# MCB-Wise-1530-v2_0_1.net
KiCad netlist of a schematic drawn in EAGLE
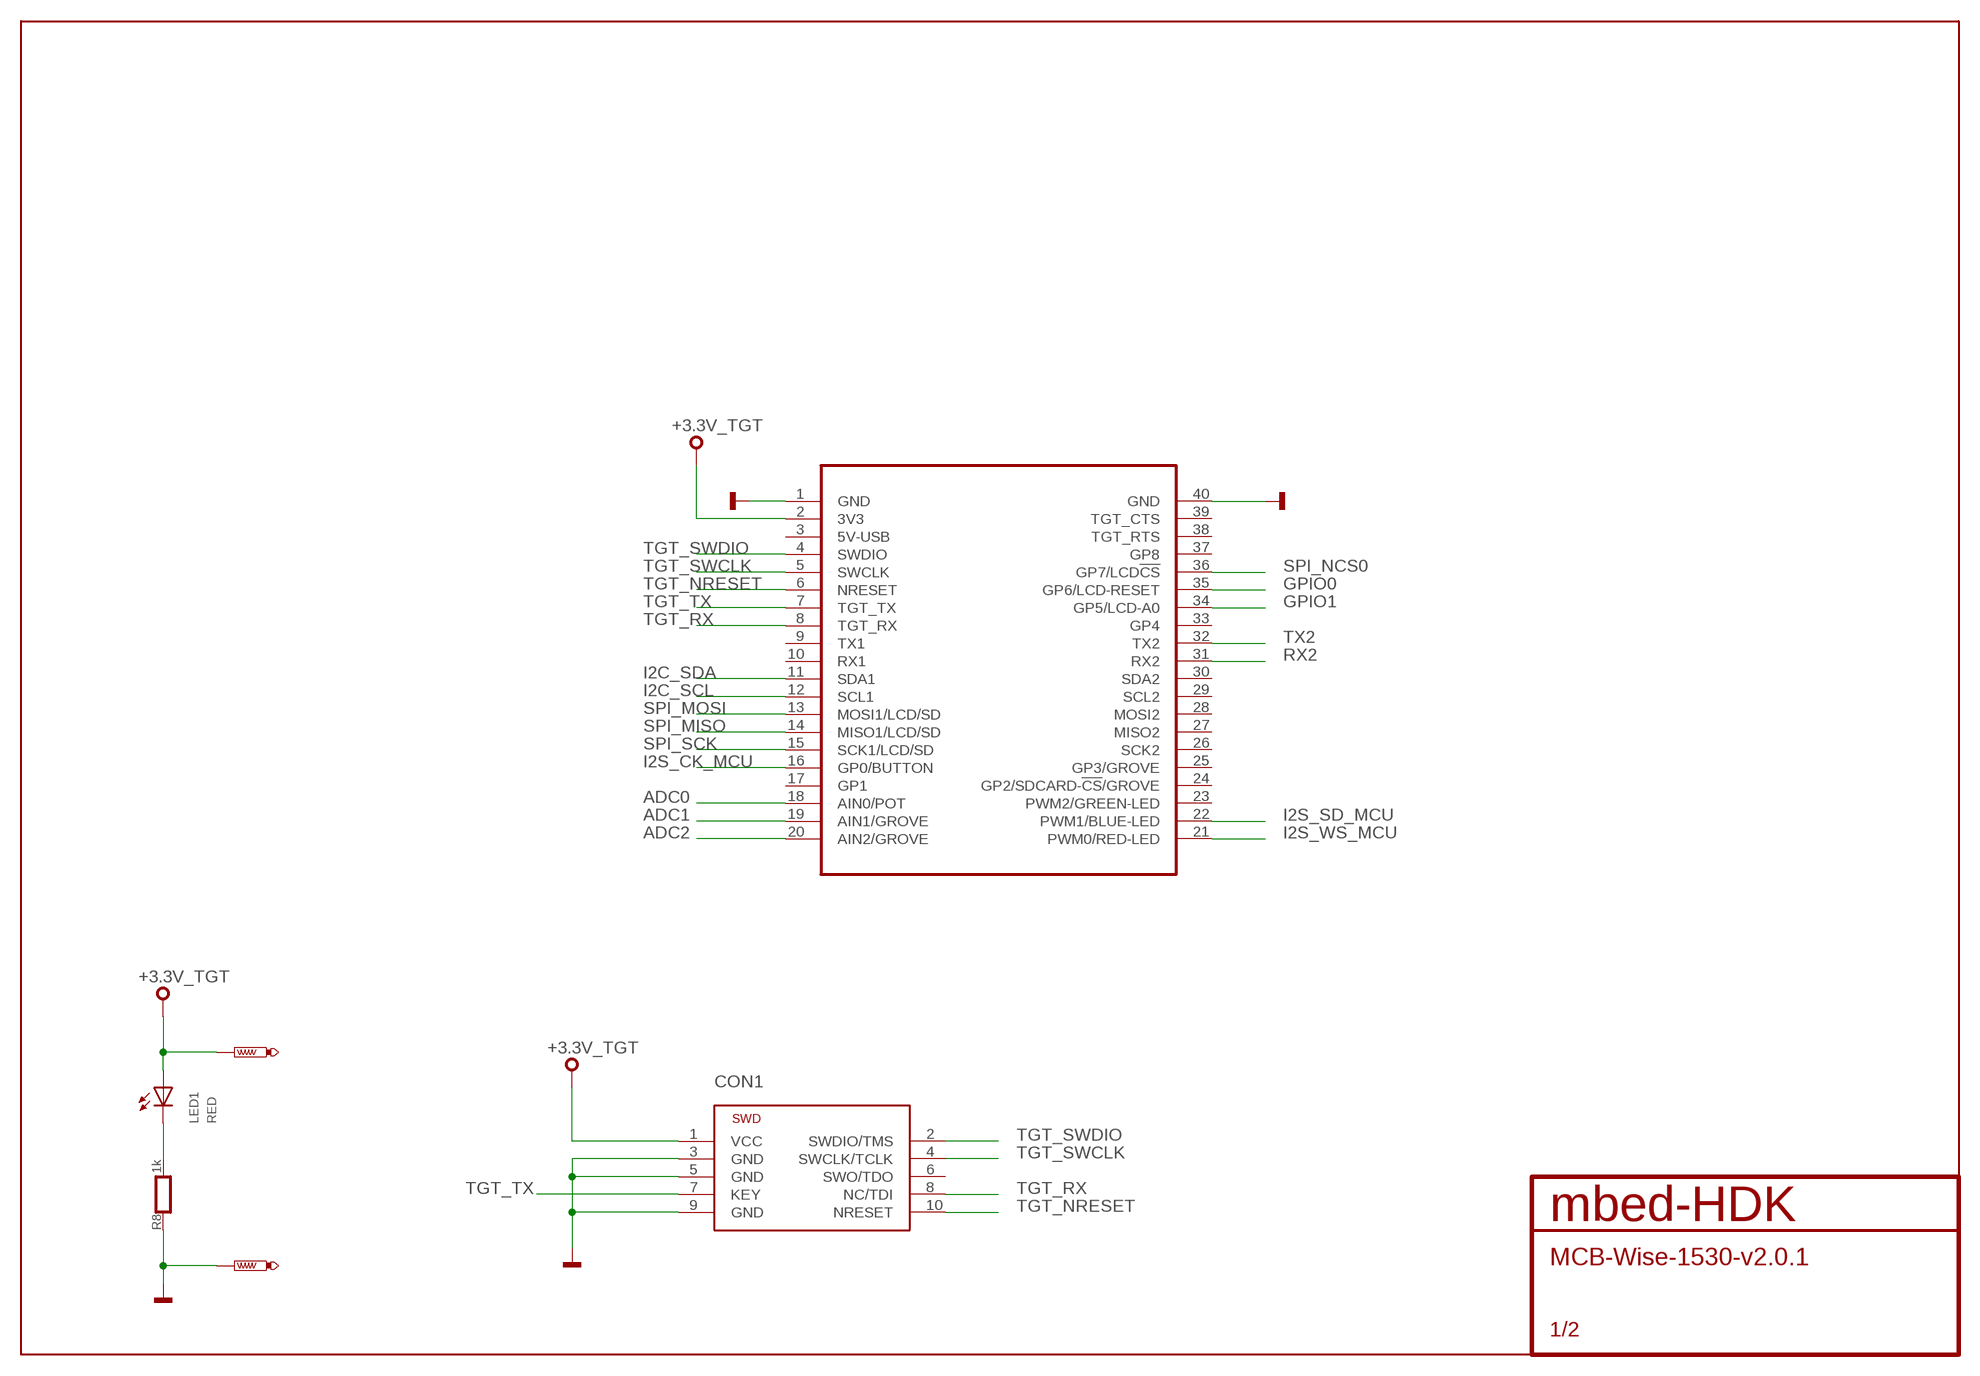
[diagram p0: schematic, sheet 1]
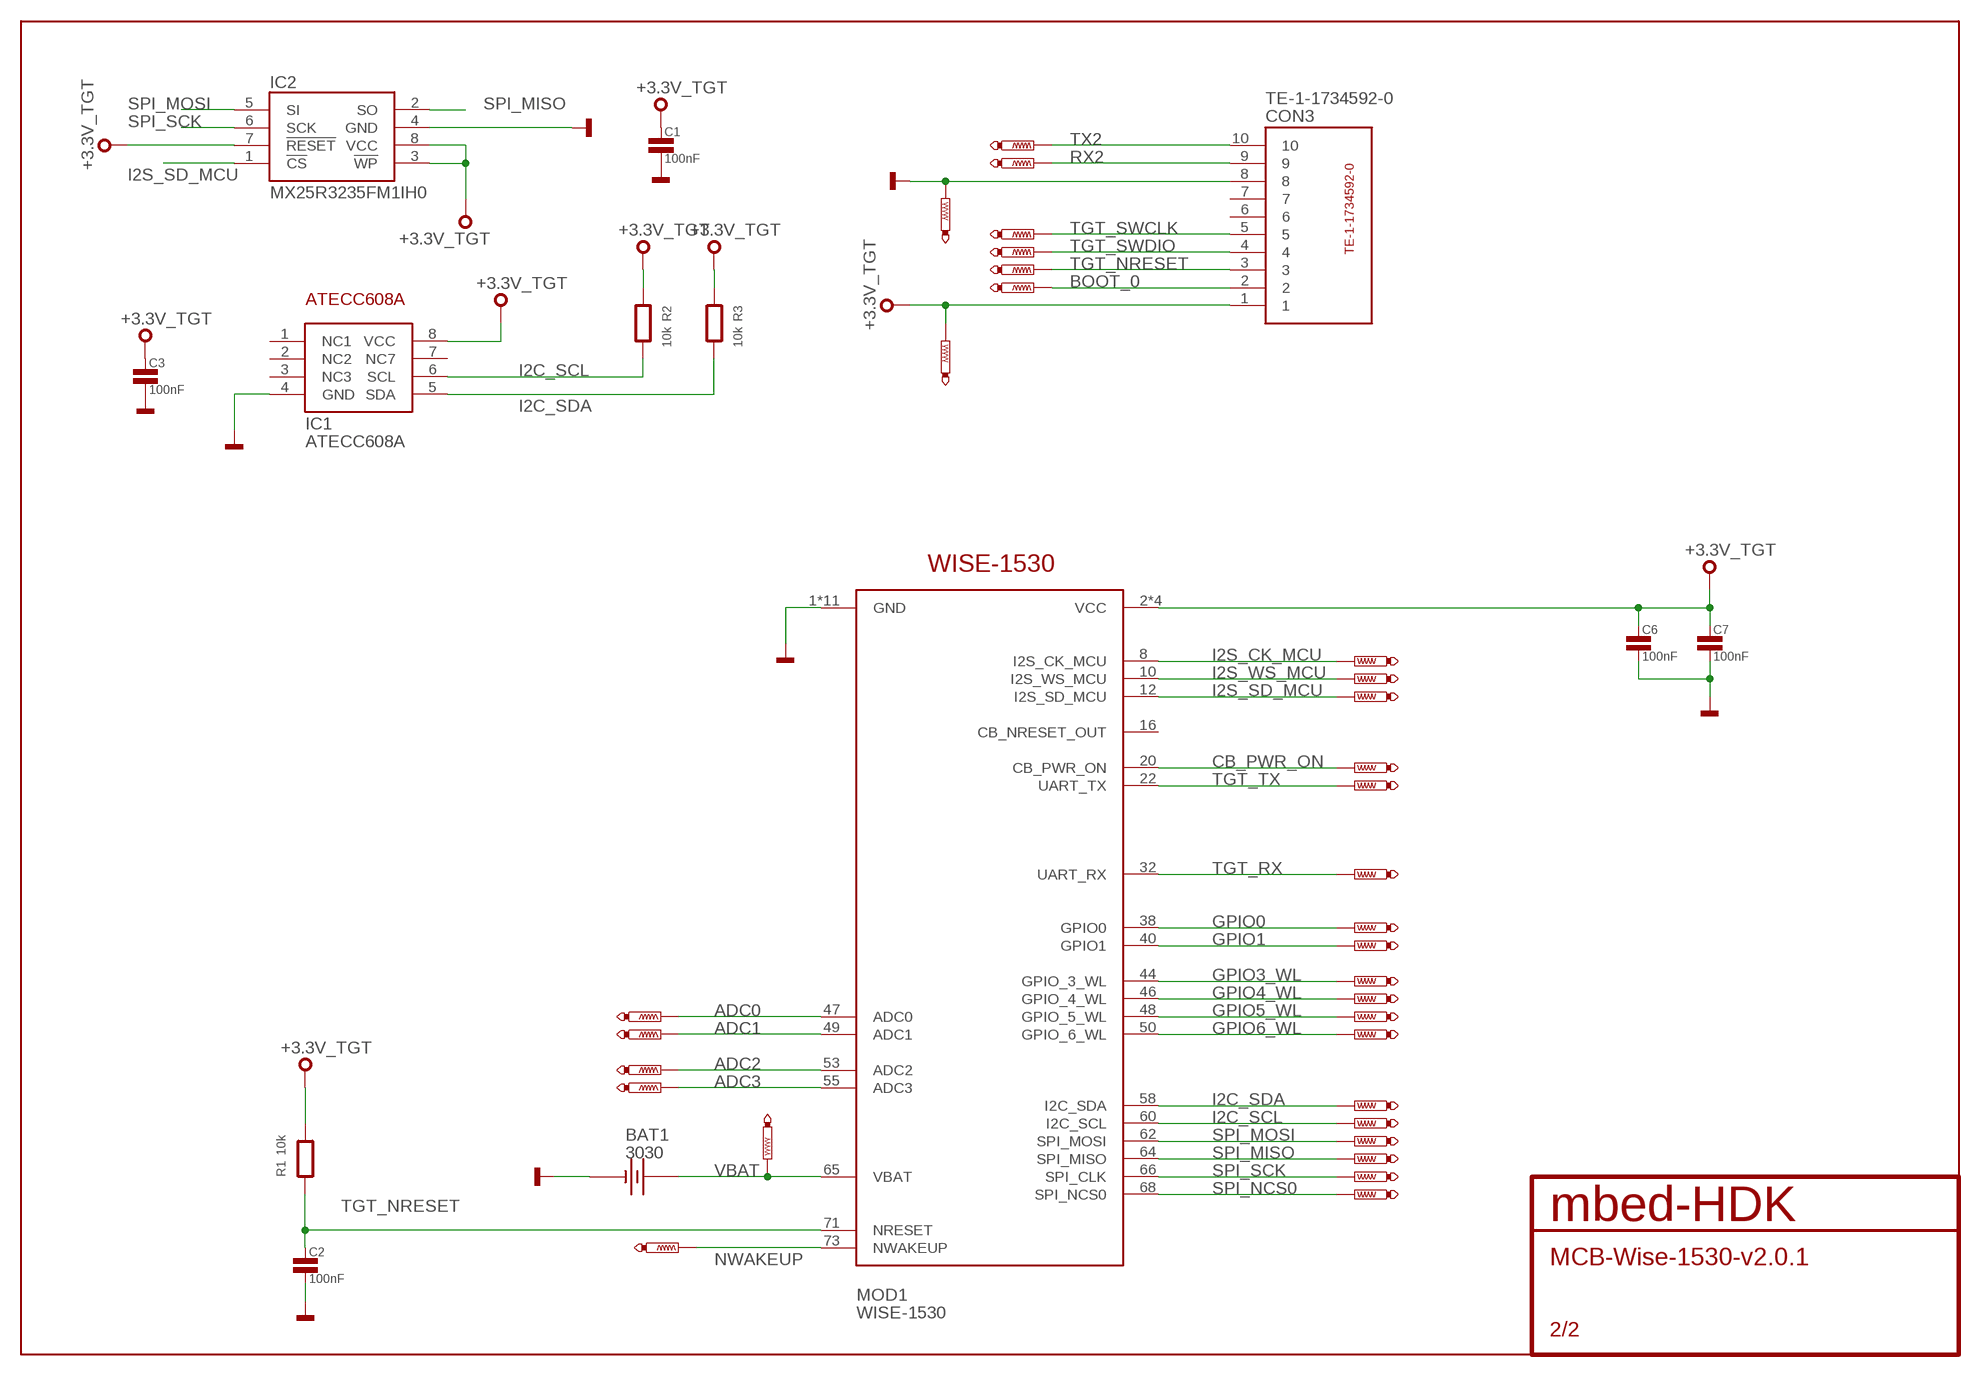
[diagram p1: schematic, sheet 2]

(export (version "E")
  (design (tool "Eeschema 10.0.6"))
  (components
    (comp (ref "CON1")
      (value "SWD-10-SMD")
      (footprint "eagle-import:SWD-10-SMD")
      (libsource (lib "eagle-import") (part "SWD-10-SMD"))
    )
    (comp (ref "LED1")
      (value "RED")
      (footprint "eagle-import:CHIPLED_0603")
      (fields (field (name "MF") "Wurth Electronics Inc"))
      (libsource (lib "eagle-import") (part "SMD_LED0603"))
    )
    (comp (ref "MOD2")
      (value "MODULE_DAUGHTER")
      (footprint "eagle-import:MODULE_DAUGHTER")
      (libsource (lib "eagle-import") (part "MODULE_DAUGHTER"))
    )
    (comp (ref "R8")
      (value "1k")
      (footprint "eagle-import:0603")
      (libsource (lib "eagle-import") (part "R0603"))
    )
    (comp (ref "TP1")
      (value "PTR1P1-10")
      (footprint "eagle-import:P1-10")
      (libsource (lib "eagle-import") (part "PTR1P1-10"))
    )
    (comp (ref "TP2")
      (value "PTR1P1-10")
      (footprint "eagle-import:P1-10")
      (libsource (lib "eagle-import") (part "PTR1P1-10"))
    )
    (comp (ref "BAT1")
      (value "3030")
      (footprint "eagle-import:3030")
      (fields (field (name "MF") "Keystone"))
      (libsource (lib "eagle-import") (part "3030"))
    )
    (comp (ref "C1")
      (value "100nF")
      (footprint "eagle-import:0603")
      (libsource (lib "eagle-import") (part "C0603"))
    )
    (comp (ref "C2")
      (value "100nF")
      (footprint "eagle-import:0603")
      (libsource (lib "eagle-import") (part "C0603"))
    )
    (comp (ref "C3")
      (value "100nF")
      (footprint "eagle-import:0603")
      (libsource (lib "eagle-import") (part "C0603"))
    )
    (comp (ref "C6")
      (value "100nF")
      (footprint "eagle-import:0603")
      (libsource (lib "eagle-import") (part "C0603"))
    )
    (comp (ref "C7")
      (value "100nF")
      (footprint "eagle-import:0603")
      (libsource (lib "eagle-import") (part "C0603"))
    )
    (comp (ref "CON3")
      (value "TE-1-1734592-0")
      (footprint "eagle-import:TE-1-1734592-0")
      (fields (field (name "MF") "TE Connectivity"))
      (libsource (lib "eagle-import") (part "TE-1-1734592-0"))
    )
    (comp (ref "IC1")
      (value "ATECC608A")
      (footprint "eagle-import:SO8")
      (fields (field (name "MF") "Atmel"))
      (libsource (lib "eagle-import") (part "ATECC608A"))
    )
    (comp (ref "IC2")
      (value "MX25R3235FM1IH0")
      (footprint "eagle-import:SO8")
      (fields (field (name "MF") "Macronix"))
      (libsource (lib "eagle-import") (part "MX25R3235FM1IH0"))
    )
    (comp (ref "MOD1")
      (value "WISE-1530")
      (footprint "eagle-import:MDT420E02001")
      (fields (field (name "MF") "Amphenol"))
      (libsource (lib "eagle-import") (part "WISE-1530"))
    )
    (comp (ref "R1")
      (value "10k")
      (footprint "eagle-import:0603")
      (libsource (lib "eagle-import") (part "R0603"))
    )
    (comp (ref "R2")
      (value "10k")
      (footprint "eagle-import:0603")
      (libsource (lib "eagle-import") (part "R0603"))
    )
    (comp (ref "R3")
      (value "10k")
      (footprint "eagle-import:0603")
      (libsource (lib "eagle-import") (part "R0603"))
    )
    (comp (ref "TP3")
      (value "PTR1TP08R")
      (footprint "eagle-import:TP08R")
      (libsource (lib "eagle-import") (part "PTR1TP08R"))
    )
    (comp (ref "TP4")
      (value "PTR1TP08R")
      (footprint "eagle-import:TP08R")
      (libsource (lib "eagle-import") (part "PTR1TP08R"))
    )
    (comp (ref "TP5")
      (value "PTR1TP08R")
      (footprint "eagle-import:TP08R")
      (libsource (lib "eagle-import") (part "PTR1TP08R"))
    )
    (comp (ref "TP6")
      (value "PTR1TP08R")
      (footprint "eagle-import:TP08R")
      (libsource (lib "eagle-import") (part "PTR1TP08R"))
    )
    (comp (ref "TP7")
      (value "PTR1TP08R")
      (footprint "eagle-import:TP08R")
      (libsource (lib "eagle-import") (part "PTR1TP08R"))
    )
    (comp (ref "TP8")
      (value "PTR1TP08R")
      (footprint "eagle-import:TP08R")
      (libsource (lib "eagle-import") (part "PTR1TP08R"))
    )
    (comp (ref "TP9")
      (value "PTR1TP08R")
      (footprint "eagle-import:TP08R")
      (libsource (lib "eagle-import") (part "PTR1TP08R"))
    )
    (comp (ref "TP10")
      (value "PTR1TP08R")
      (footprint "eagle-import:TP08R")
      (libsource (lib "eagle-import") (part "PTR1TP08R"))
    )
    (comp (ref "TP11")
      (value "PTR1TP08R")
      (footprint "eagle-import:TP08R")
      (libsource (lib "eagle-import") (part "PTR1TP08R"))
    )
    (comp (ref "TP12")
      (value "PTR1TP08R")
      (footprint "eagle-import:TP08R")
      (libsource (lib "eagle-import") (part "PTR1TP08R"))
    )
    (comp (ref "TP13")
      (value "PTR1TP08R")
      (footprint "eagle-import:TP08R")
      (libsource (lib "eagle-import") (part "PTR1TP08R"))
    )
    (comp (ref "TP14")
      (value "PTR1TP08R")
      (footprint "eagle-import:TP08R")
      (libsource (lib "eagle-import") (part "PTR1TP08R"))
    )
    (comp (ref "TP15")
      (value "PTR1TP08R")
      (footprint "eagle-import:TP08R")
      (libsource (lib "eagle-import") (part "PTR1TP08R"))
    )
    (comp (ref "TP16")
      (value "PTR1TP08R")
      (footprint "eagle-import:TP08R")
      (libsource (lib "eagle-import") (part "PTR1TP08R"))
    )
    (comp (ref "TP17")
      (value "PTR1TP08R")
      (footprint "eagle-import:TP08R")
      (libsource (lib "eagle-import") (part "PTR1TP08R"))
    )
    (comp (ref "TP18")
      (value "PTR1TP08R")
      (footprint "eagle-import:TP08R")
      (libsource (lib "eagle-import") (part "PTR1TP08R"))
    )
    (comp (ref "TP19")
      (value "PTR1TP08R")
      (footprint "eagle-import:TP08R")
      (libsource (lib "eagle-import") (part "PTR1TP08R"))
    )
    (comp (ref "TP20")
      (value "PTR1TP08R")
      (footprint "eagle-import:TP08R")
      (libsource (lib "eagle-import") (part "PTR1TP08R"))
    )
    (comp (ref "TP21")
      (value "PTR1TP08R")
      (footprint "eagle-import:TP08R")
      (libsource (lib "eagle-import") (part "PTR1TP08R"))
    )
    (comp (ref "TP22")
      (value "PTR1TP08R")
      (footprint "eagle-import:TP08R")
      (libsource (lib "eagle-import") (part "PTR1TP08R"))
    )
    (comp (ref "TP23")
      (value "PTR1TP08R")
      (footprint "eagle-import:TP08R")
      (libsource (lib "eagle-import") (part "PTR1TP08R"))
    )
    (comp (ref "TP24")
      (value "PTR1TP08R")
      (footprint "eagle-import:TP08R")
      (libsource (lib "eagle-import") (part "PTR1TP08R"))
    )
    (comp (ref "TP25")
      (value "PTR1TP08R")
      (footprint "eagle-import:TP08R")
      (libsource (lib "eagle-import") (part "PTR1TP08R"))
    )
    (comp (ref "TP26")
      (value "PTR1TP08R")
      (footprint "eagle-import:TP08R")
      (libsource (lib "eagle-import") (part "PTR1TP08R"))
    )
    (comp (ref "TP27")
      (value "PTR1TP08R")
      (footprint "eagle-import:TP08R")
      (libsource (lib "eagle-import") (part "PTR1TP08R"))
    )
    (comp (ref "TP28")
      (value "PTR1TP08R")
      (footprint "eagle-import:TP08R")
      (libsource (lib "eagle-import") (part "PTR1TP08R"))
    )
    (comp (ref "TP29")
      (value "PTR1TP08R")
      (footprint "eagle-import:TP08R")
      (libsource (lib "eagle-import") (part "PTR1TP08R"))
    )
    (comp (ref "TP30")
      (value "PTR1TP08R")
      (footprint "eagle-import:TP08R")
      (libsource (lib "eagle-import") (part "PTR1TP08R"))
    )
    (comp (ref "TP31")
      (value "PTR1TP08R")
      (footprint "eagle-import:TP08R")
      (libsource (lib "eagle-import") (part "PTR1TP08R"))
    )
    (comp (ref "TP32")
      (value "PTR1TP08R")
      (footprint "eagle-import:TP08R")
      (libsource (lib "eagle-import") (part "PTR1TP08R"))
    )
    (comp (ref "TP33")
      (value "PTR1TP08R")
      (footprint "eagle-import:TP08R")
      (libsource (lib "eagle-import") (part "PTR1TP08R"))
    )
    (comp (ref "TP34")
      (value "PTR1TP08R")
      (footprint "eagle-import:TP08R")
      (libsource (lib "eagle-import") (part "PTR1TP08R"))
    )
  )
  (nets
    (net (code "1") (name "+3.3V_TGT") (class "Default")
      (node (ref "C1") (pin "1") (pinfunction "P$1_1") (pintype "passive"))
      (node (ref "C3") (pin "1") (pinfunction "P$1_1") (pintype "passive"))
      (node (ref "C6") (pin "1") (pinfunction "P$1_1") (pintype "passive"))
      (node (ref "C7") (pin "1") (pinfunction "P$1_1") (pintype "passive"))
      (node (ref "CON1") (pin "1") (pinfunction "VCC_1") (pintype "bidirectional"))
      (node (ref "CON3") (pin "1") (pinfunction "1_1") (pintype "bidirectional"))
      (node (ref "IC1") (pin "8") (pinfunction "VCC_8") (pintype "bidirectional"))
      (node (ref "IC2") (pin "3") (pinfunction "~{WP}_3") (pintype "bidirectional"))
      (node (ref "IC2") (pin "7") (pinfunction "~{RESET}_7") (pintype "bidirectional"))
      (node (ref "IC2") (pin "8") (pinfunction "VCC_8") (pintype "bidirectional"))
      (node (ref "LED1") (pin "A") (pinfunction "A_A") (pintype "passive"))
      (node (ref "MOD1") (pin "2") (pinfunction "VCC_2") (pintype "bidirectional"))
      (node (ref "MOD1") (pin "4") (pinfunction "VCC_4") (pintype "bidirectional"))
      (node (ref "MOD1") (pin "72") (pinfunction "VCC_72") (pintype "bidirectional"))
      (node (ref "MOD1") (pin "74") (pinfunction "VCC_74") (pintype "bidirectional"))
      (node (ref "MOD2") (pin "2") (pinfunction "3V3_2") (pintype "bidirectional"))
      (node (ref "R1") (pin "2") (pinfunction "P$2_2") (pintype "passive"))
      (node (ref "R2") (pin "1") (pinfunction "P$1_1") (pintype "passive"))
      (node (ref "R3") (pin "1") (pinfunction "P$1_1") (pintype "passive"))
      (node (ref "TP1") (pin "TP") (pinfunction "TP_TP") (pintype "input"))
      (node (ref "TP12") (pin "TP") (pinfunction "TP_TP") (pintype "input"))
    )
    (net (code "2") (name "ADC0") (class "Default")
      (node (ref "MOD1") (pin "47") (pinfunction "ADC0_47") (pintype "bidirectional"))
      (node (ref "MOD2") (pin "18") (pinfunction "AIN0/POT_18") (pintype "bidirectional"))
      (node (ref "TP29") (pin "TP") (pinfunction "TP_TP") (pintype "input"))
    )
    (net (code "3") (name "ADC1") (class "Default")
      (node (ref "MOD1") (pin "49") (pinfunction "ADC1_49") (pintype "bidirectional"))
      (node (ref "MOD2") (pin "19") (pinfunction "AIN1/GROVE_19") (pintype "bidirectional"))
      (node (ref "TP30") (pin "TP") (pinfunction "TP_TP") (pintype "input"))
    )
    (net (code "4") (name "ADC2") (class "Default")
      (node (ref "MOD1") (pin "53") (pinfunction "ADC2_53") (pintype "bidirectional"))
      (node (ref "MOD2") (pin "20") (pinfunction "AIN2/GROVE_20") (pintype "bidirectional"))
      (node (ref "TP31") (pin "TP") (pinfunction "TP_TP") (pintype "input"))
    )
    (net (code "5") (name "ADC3") (class "Default")
      (node (ref "MOD1") (pin "55") (pinfunction "ADC3_55") (pintype "bidirectional"))
      (node (ref "TP32") (pin "TP") (pinfunction "TP_TP") (pintype "input"))
    )
    (net (code "6") (name "BOOT_0") (class "Default")
      (node (ref "CON3") (pin "2") (pinfunction "2_2") (pintype "bidirectional"))
      (node (ref "TP8") (pin "TP") (pinfunction "TP_TP") (pintype "input"))
    )
    (net (code "7") (name "CB_PWR_ON") (class "Default")
      (node (ref "MOD1") (pin "20") (pinfunction "CB_PWR_ON_20") (pintype "bidirectional"))
      (node (ref "TP14") (pin "TP") (pinfunction "TP_TP") (pintype "input"))
    )
    (net (code "8") (name "GND") (class "Default")
      (node (ref "BAT1") (pin "NEG") (pinfunction "-_NEG") (pintype "bidirectional"))
      (node (ref "C1") (pin "2") (pinfunction "P$2_2") (pintype "passive"))
      (node (ref "C2") (pin "2") (pinfunction "P$2_2") (pintype "passive"))
      (node (ref "C3") (pin "2") (pinfunction "P$2_2") (pintype "passive"))
      (node (ref "C6") (pin "2") (pinfunction "P$2_2") (pintype "passive"))
      (node (ref "C7") (pin "2") (pinfunction "P$2_2") (pintype "passive"))
      (node (ref "CON1") (pin "3") (pinfunction "GND_3") (pintype "bidirectional"))
      (node (ref "CON1") (pin "5") (pinfunction "GND_5") (pintype "bidirectional"))
      (node (ref "CON1") (pin "9") (pinfunction "GND_9") (pintype "bidirectional"))
      (node (ref "CON3") (pin "8") (pinfunction "8_8") (pintype "bidirectional"))
      (node (ref "IC1") (pin "4") (pinfunction "GND_4") (pintype "bidirectional"))
      (node (ref "IC2") (pin "4") (pinfunction "GND_4") (pintype "bidirectional"))
      (node (ref "MOD1") (pin "1") (pinfunction "GND_1") (pintype "bidirectional"))
      (node (ref "MOD1") (pin "18") (pinfunction "GND_18") (pintype "bidirectional"))
      (node (ref "MOD1") (pin "33") (pinfunction "GND_33") (pintype "bidirectional"))
      (node (ref "MOD1") (pin "39") (pinfunction "GND_39") (pintype "bidirectional"))
      (node (ref "MOD1") (pin "45") (pinfunction "GND_45") (pintype "bidirectional"))
      (node (ref "MOD1") (pin "51") (pinfunction "GND_51") (pintype "bidirectional"))
      (node (ref "MOD1") (pin "57") (pinfunction "GND_57") (pintype "bidirectional"))
      (node (ref "MOD1") (pin "63") (pinfunction "GND_63") (pintype "bidirectional"))
      (node (ref "MOD1") (pin "69") (pinfunction "GND_69") (pintype "bidirectional"))
      (node (ref "MOD1") (pin "7") (pinfunction "GND_7") (pintype "bidirectional"))
      (node (ref "MOD1") (pin "75") (pinfunction "GND_75") (pintype "bidirectional"))
      (node (ref "MOD2") (pin "1") (pinfunction "GND_1") (pintype "bidirectional"))
      (node (ref "MOD2") (pin "40") (pinfunction "GND_40") (pintype "bidirectional"))
      (node (ref "R8") (pin "1") (pinfunction "P$1_1") (pintype "passive"))
      (node (ref "TP13") (pin "TP") (pinfunction "TP_TP") (pintype "input"))
      (node (ref "TP2") (pin "TP") (pinfunction "TP_TP") (pintype "input"))
    )
    (net (code "9") (name "GPIO0") (class "Default")
      (node (ref "MOD1") (pin "38") (pinfunction "GPIO0_38") (pintype "bidirectional"))
      (node (ref "MOD2") (pin "35") (pinfunction "GP6/LCD-RESET_35") (pintype "bidirectional"))
      (node (ref "TP27") (pin "TP") (pinfunction "TP_TP") (pintype "input"))
    )
    (net (code "10") (name "GPIO1") (class "Default")
      (node (ref "MOD1") (pin "40") (pinfunction "GPIO1_40") (pintype "bidirectional"))
      (node (ref "MOD2") (pin "34") (pinfunction "GP5/LCD-A0_34") (pintype "bidirectional"))
      (node (ref "TP26") (pin "TP") (pinfunction "TP_TP") (pintype "input"))
    )
    (net (code "11") (name "GPIO3_WL") (class "Default")
      (node (ref "MOD1") (pin "44") (pinfunction "GPIO_3_WL_44") (pintype "bidirectional"))
      (node (ref "TP25") (pin "TP") (pinfunction "TP_TP") (pintype "input"))
    )
    (net (code "12") (name "GPIO4_WL") (class "Default")
      (node (ref "MOD1") (pin "46") (pinfunction "GPIO_4_WL_46") (pintype "bidirectional"))
      (node (ref "TP24") (pin "TP") (pinfunction "TP_TP") (pintype "input"))
    )
    (net (code "13") (name "GPIO5_WL") (class "Default")
      (node (ref "MOD1") (pin "48") (pinfunction "GPIO_5_WL_48") (pintype "bidirectional"))
      (node (ref "TP23") (pin "TP") (pinfunction "TP_TP") (pintype "input"))
    )
    (net (code "14") (name "GPIO6_WL") (class "Default")
      (node (ref "MOD1") (pin "50") (pinfunction "GPIO_6_WL_50") (pintype "bidirectional"))
      (node (ref "TP22") (pin "TP") (pinfunction "TP_TP") (pintype "input"))
    )
    (net (code "15") (name "I2C_SCL") (class "Default")
      (node (ref "IC1") (pin "6") (pinfunction "SCL_6") (pintype "bidirectional"))
      (node (ref "MOD1") (pin "60") (pinfunction "I2C_SCL_60") (pintype "bidirectional"))
      (node (ref "MOD2") (pin "12") (pinfunction "SCL1_12") (pintype "bidirectional"))
      (node (ref "R2") (pin "2") (pinfunction "P$2_2") (pintype "passive"))
      (node (ref "TP20") (pin "TP") (pinfunction "TP_TP") (pintype "input"))
    )
    (net (code "16") (name "I2C_SDA") (class "Default")
      (node (ref "IC1") (pin "5") (pinfunction "SDA_5") (pintype "bidirectional"))
      (node (ref "MOD1") (pin "58") (pinfunction "I2C_SDA_58") (pintype "bidirectional"))
      (node (ref "MOD2") (pin "11") (pinfunction "SDA1_11") (pintype "bidirectional"))
      (node (ref "R3") (pin "2") (pinfunction "P$2_2") (pintype "passive"))
      (node (ref "TP21") (pin "TP") (pinfunction "TP_TP") (pintype "input"))
    )
    (net (code "17") (name "I2S_CK_MCU") (class "Default")
      (node (ref "MOD1") (pin "8") (pinfunction "I2S_CK_MCU_8") (pintype "bidirectional"))
      (node (ref "MOD2") (pin "16") (pinfunction "GP0/BUTTON_16") (pintype "bidirectional"))
      (node (ref "TP9") (pin "TP") (pinfunction "TP_TP") (pintype "input"))
    )
    (net (code "18") (name "I2S_SD_MCU") (class "Default")
      (node (ref "IC2") (pin "1") (pinfunction "~{CS}_1") (pintype "bidirectional"))
      (node (ref "MOD1") (pin "12") (pinfunction "I2S_SD_MCU_12") (pintype "bidirectional"))
      (node (ref "MOD2") (pin "22") (pinfunction "PWM1/BLUE-LED_22") (pintype "bidirectional"))
      (node (ref "TP11") (pin "TP") (pinfunction "TP_TP") (pintype "input"))
    )
    (net (code "19") (name "I2S_WS_MCU") (class "Default")
      (node (ref "MOD1") (pin "10") (pinfunction "I2S_WS_MCU_10") (pintype "bidirectional"))
      (node (ref "MOD2") (pin "21") (pinfunction "PWM0/RED-LED_21") (pintype "bidirectional"))
      (node (ref "TP10") (pin "TP") (pinfunction "TP_TP") (pintype "input"))
    )
    (net (code "20") (name "NWAKEUP") (class "Default")
      (node (ref "MOD1") (pin "73") (pinfunction "NWAKEUP_73") (pintype "bidirectional"))
      (node (ref "TP34") (pin "TP") (pinfunction "TP_TP") (pintype "input"))
    )
    (net (code "21") (name "Net-(R8-P$2)") (class "Default")
      (node (ref "LED1") (pin "C") (pinfunction "C_C") (pintype "passive"))
      (node (ref "R8") (pin "2") (pinfunction "P$2_2") (pintype "passive"))
    )
    (net (code "22") (name "RX2") (class "Default")
      (node (ref "CON3") (pin "9") (pinfunction "9_9") (pintype "bidirectional"))
      (node (ref "MOD2") (pin "31") (pinfunction "RX2_31") (pintype "bidirectional"))
      (node (ref "TP6") (pin "TP") (pinfunction "TP_TP") (pintype "input"))
    )
    (net (code "23") (name "SPI_MISO") (class "Default")
      (node (ref "IC2") (pin "2") (pinfunction "SO_2") (pintype "bidirectional"))
      (node (ref "MOD1") (pin "64") (pinfunction "SPI_MISO_64") (pintype "bidirectional"))
      (node (ref "MOD2") (pin "14") (pinfunction "MISO1/LCD/SD_14") (pintype "bidirectional"))
      (node (ref "TP18") (pin "TP") (pinfunction "TP_TP") (pintype "input"))
    )
    (net (code "24") (name "SPI_MOSI") (class "Default")
      (node (ref "IC2") (pin "5") (pinfunction "SI_5") (pintype "bidirectional"))
      (node (ref "MOD1") (pin "62") (pinfunction "SPI_MOSI_62") (pintype "bidirectional"))
      (node (ref "MOD2") (pin "13") (pinfunction "MOSI1/LCD/SD_13") (pintype "bidirectional"))
      (node (ref "TP19") (pin "TP") (pinfunction "TP_TP") (pintype "input"))
    )
    (net (code "25") (name "SPI_NCS0") (class "Default")
      (node (ref "MOD1") (pin "68") (pinfunction "SPI_NCS0_68") (pintype "bidirectional"))
      (node (ref "MOD2") (pin "36") (pinfunction "GP7/LCD~{CS}_36") (pintype "bidirectional"))
      (node (ref "TP16") (pin "TP") (pinfunction "TP_TP") (pintype "input"))
    )
    (net (code "26") (name "SPI_SCK") (class "Default")
      (node (ref "IC2") (pin "6") (pinfunction "SCK_6") (pintype "bidirectional"))
      (node (ref "MOD1") (pin "66") (pinfunction "SPI_CLK_66") (pintype "bidirectional"))
      (node (ref "MOD2") (pin "15") (pinfunction "SCK1/LCD/SD_15") (pintype "bidirectional"))
      (node (ref "TP17") (pin "TP") (pinfunction "TP_TP") (pintype "input"))
    )
    (net (code "27") (name "TGT_NRESET") (class "Default")
      (node (ref "C2") (pin "1") (pinfunction "P$1_1") (pintype "passive"))
      (node (ref "CON1") (pin "10") (pinfunction "NRESET_10") (pintype "bidirectional"))
      (node (ref "CON3") (pin "3") (pinfunction "3_3") (pintype "bidirectional"))
      (node (ref "MOD1") (pin "71") (pinfunction "NRESET_71") (pintype "bidirectional"))
      (node (ref "MOD2") (pin "6") (pinfunction "NRESET_6") (pintype "bidirectional"))
      (node (ref "R1") (pin "1") (pinfunction "P$1_1") (pintype "passive"))
      (node (ref "TP5") (pin "TP") (pinfunction "TP_TP") (pintype "input"))
    )
    (net (code "28") (name "TGT_RX") (class "Default")
      (node (ref "CON1") (pin "8") (pinfunction "NC/TDI_8") (pintype "bidirectional"))
      (node (ref "MOD1") (pin "32") (pinfunction "UART_RX_32") (pintype "bidirectional"))
      (node (ref "MOD2") (pin "8") (pinfunction "TGT_RX_8") (pintype "bidirectional"))
      (node (ref "TP28") (pin "TP") (pinfunction "TP_TP") (pintype "input"))
    )
    (net (code "29") (name "TGT_SWCLK") (class "Default")
      (node (ref "CON1") (pin "4") (pinfunction "SWCLK/TCLK_4") (pintype "bidirectional"))
      (node (ref "CON3") (pin "5") (pinfunction "5_5") (pintype "bidirectional"))
      (node (ref "MOD2") (pin "5") (pinfunction "SWCLK_5") (pintype "bidirectional"))
      (node (ref "TP3") (pin "TP") (pinfunction "TP_TP") (pintype "input"))
    )
    (net (code "30") (name "TGT_SWDIO") (class "Default")
      (node (ref "CON1") (pin "2") (pinfunction "SWDIO/TMS_2") (pintype "bidirectional"))
      (node (ref "CON3") (pin "4") (pinfunction "4_4") (pintype "bidirectional"))
      (node (ref "MOD2") (pin "4") (pinfunction "SWDIO_4") (pintype "bidirectional"))
      (node (ref "TP4") (pin "TP") (pinfunction "TP_TP") (pintype "input"))
    )
    (net (code "31") (name "TGT_TX") (class "Default")
      (node (ref "CON1") (pin "7") (pinfunction "KEY_7") (pintype "bidirectional"))
      (node (ref "MOD1") (pin "22") (pinfunction "UART_TX_22") (pintype "bidirectional"))
      (node (ref "MOD2") (pin "7") (pinfunction "TGT_TX_7") (pintype "bidirectional"))
      (node (ref "TP15") (pin "TP") (pinfunction "TP_TP") (pintype "input"))
    )
    (net (code "32") (name "TX2") (class "Default")
      (node (ref "CON3") (pin "10") (pinfunction "10_10") (pintype "bidirectional"))
      (node (ref "MOD2") (pin "32") (pinfunction "TX2_32") (pintype "bidirectional"))
      (node (ref "TP7") (pin "TP") (pinfunction "TP_TP") (pintype "input"))
    )
    (net (code "33") (name "VBAT") (class "Default")
      (node (ref "BAT1") (pin "P$1") (pinfunction "+_P$1") (pintype "bidirectional"))
      (node (ref "BAT1") (pin "P$2") (pinfunction "+_P$2") (pintype "bidirectional"))
      (node (ref "MOD1") (pin "65") (pinfunction "VBAT_65") (pintype "bidirectional"))
      (node (ref "TP33") (pin "TP") (pinfunction "TP_TP") (pintype "input"))
    )
    (net (code "34") (name "unconnected-(CON1-SWO{slash}TDO-Pad6)") (class "Default")
      (node (ref "CON1") (pin "6") (pinfunction "SWO/TDO_6") (pintype "bidirectional"))
    )
    (net (code "35") (name "unconnected-(CON3-Pad6)") (class "Default")
      (node (ref "CON3") (pin "6") (pinfunction "6_6") (pintype "bidirectional"))
    )
    (net (code "36") (name "unconnected-(CON3-Pad7)") (class "Default")
      (node (ref "CON3") (pin "7") (pinfunction "7_7") (pintype "bidirectional"))
    )
    (net (code "37") (name "unconnected-(IC1-NC1-Pad1)") (class "Default")
      (node (ref "IC1") (pin "1") (pinfunction "NC1_1") (pintype "bidirectional"))
    )
    (net (code "38") (name "unconnected-(IC1-NC2-Pad2)") (class "Default")
      (node (ref "IC1") (pin "2") (pinfunction "NC2_2") (pintype "bidirectional"))
    )
    (net (code "39") (name "unconnected-(IC1-NC3-Pad3)") (class "Default")
      (node (ref "IC1") (pin "3") (pinfunction "NC3_3") (pintype "bidirectional"))
    )
    (net (code "40") (name "unconnected-(IC1-NC7-Pad7)") (class "Default")
      (node (ref "IC1") (pin "7") (pinfunction "NC7_7") (pintype "bidirectional"))
    )
    (net (code "41") (name "unconnected-(MOD1-CB_NRESET_OUT-Pad16)") (class "Default")
      (node (ref "MOD1") (pin "16") (pinfunction "CB_NRESET_OUT_16") (pintype "bidirectional"))
    )
    (net (code "42") (name "unconnected-(MOD2-5V-USB-Pad3)") (class "Default")
      (node (ref "MOD2") (pin "3") (pinfunction "5V-USB_3") (pintype "bidirectional"))
    )
    (net (code "43") (name "unconnected-(MOD2-GP1-Pad17)") (class "Default")
      (node (ref "MOD2") (pin "17") (pinfunction "GP1_17") (pintype "bidirectional"))
    )
    (net (code "44") (name "unconnected-(MOD2-GP2{slash}SDCARD-~{CS}{slash}GROVE-Pad24)") (class "Default")
      (node (ref "MOD2") (pin "24") (pinfunction "GP2/SDCARD-~{CS}/GROVE_24") (pintype "bidirectional"))
    )
    (net (code "45") (name "unconnected-(MOD2-GP3{slash}GROVE-Pad25)") (class "Default")
      (node (ref "MOD2") (pin "25") (pinfunction "GP3/GROVE_25") (pintype "bidirectional"))
    )
    (net (code "46") (name "unconnected-(MOD2-GP4-Pad33)") (class "Default")
      (node (ref "MOD2") (pin "33") (pinfunction "GP4_33") (pintype "bidirectional"))
    )
    (net (code "47") (name "unconnected-(MOD2-GP8-Pad37)") (class "Default")
      (node (ref "MOD2") (pin "37") (pinfunction "GP8_37") (pintype "bidirectional"))
    )
    (net (code "48") (name "unconnected-(MOD2-MISO2-Pad27)") (class "Default")
      (node (ref "MOD2") (pin "27") (pinfunction "MISO2_27") (pintype "bidirectional"))
    )
    (net (code "49") (name "unconnected-(MOD2-MOSI2-Pad28)") (class "Default")
      (node (ref "MOD2") (pin "28") (pinfunction "MOSI2_28") (pintype "bidirectional"))
    )
    (net (code "50") (name "unconnected-(MOD2-PWM2{slash}GREEN-LED-Pad23)") (class "Default")
      (node (ref "MOD2") (pin "23") (pinfunction "PWM2/GREEN-LED_23") (pintype "bidirectional"))
    )
    (net (code "51") (name "unconnected-(MOD2-RX1-Pad10)") (class "Default")
      (node (ref "MOD2") (pin "10") (pinfunction "RX1_10") (pintype "bidirectional"))
    )
    (net (code "52") (name "unconnected-(MOD2-SCK2-Pad26)") (class "Default")
      (node (ref "MOD2") (pin "26") (pinfunction "SCK2_26") (pintype "bidirectional"))
    )
    (net (code "53") (name "unconnected-(MOD2-SCL2-Pad29)") (class "Default")
      (node (ref "MOD2") (pin "29") (pinfunction "SCL2_29") (pintype "bidirectional"))
    )
    (net (code "54") (name "unconnected-(MOD2-SDA2-Pad30)") (class "Default")
      (node (ref "MOD2") (pin "30") (pinfunction "SDA2_30") (pintype "bidirectional"))
    )
    (net (code "55") (name "unconnected-(MOD2-TGT_CTS-Pad39)") (class "Default")
      (node (ref "MOD2") (pin "39") (pinfunction "TGT_CTS_39") (pintype "bidirectional"))
    )
    (net (code "56") (name "unconnected-(MOD2-TGT_RTS-Pad38)") (class "Default")
      (node (ref "MOD2") (pin "38") (pinfunction "TGT_RTS_38") (pintype "bidirectional"))
    )
    (net (code "57") (name "unconnected-(MOD2-TX1-Pad9)") (class "Default")
      (node (ref "MOD2") (pin "9") (pinfunction "TX1_9") (pintype "bidirectional"))
    )
  )
)
